# CCM_0020_transmitter.net
KiCad netlist of a schematic drawn in EAGLE
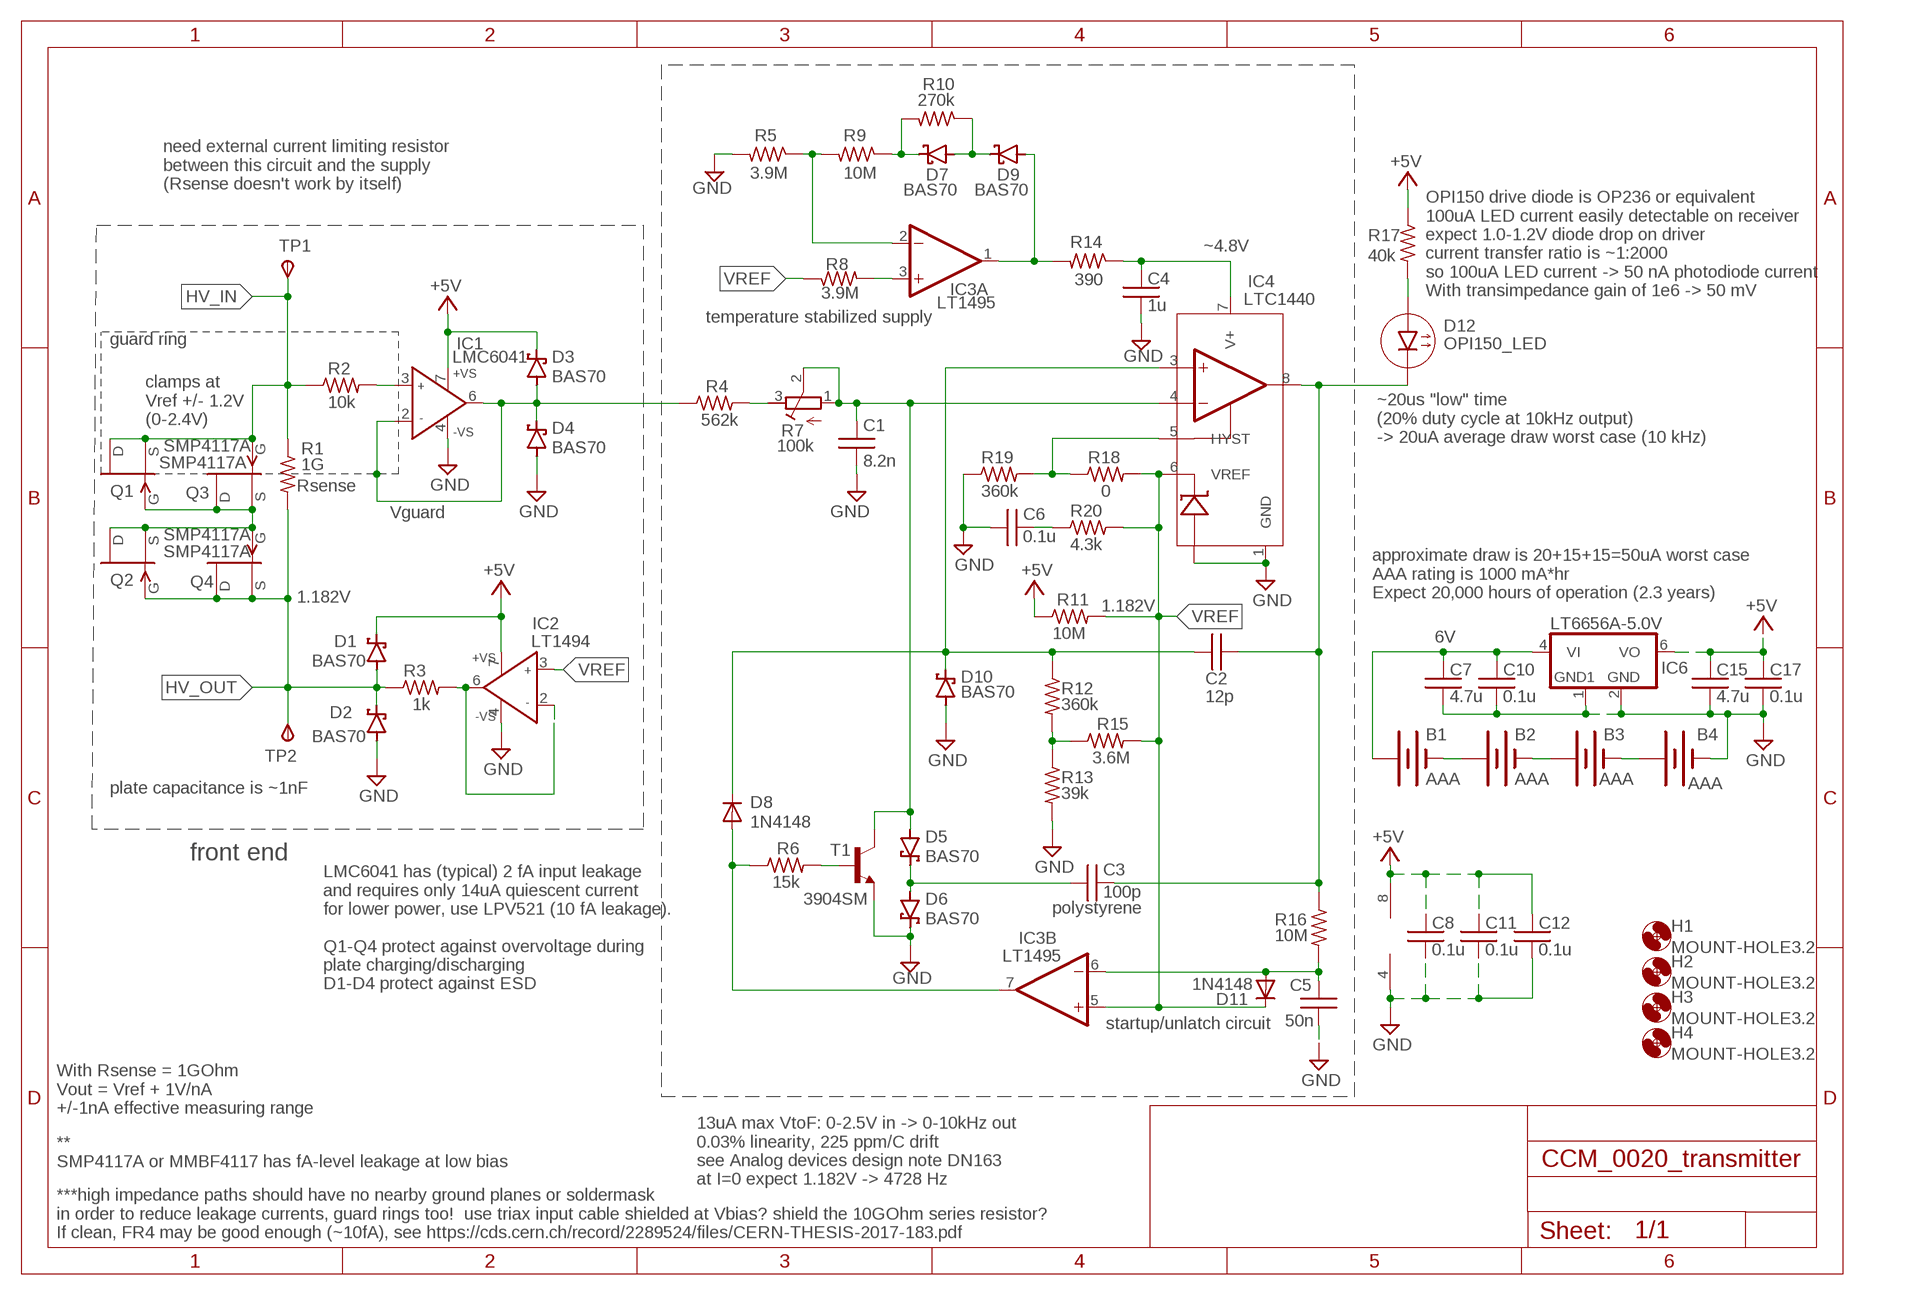
[diagram p0: schematic, sheet 1]

(export (version "E")
  (design (tool "Eeschema 10.0.6"))
  (components
    (comp (ref "B1")
      (value "AAA")
      (footprint "eagle-import:AAA_SM")
      (libsource (lib "eagle-import") (part "AAA"))
    )
    (comp (ref "B2")
      (value "AAA")
      (footprint "eagle-import:AAA_SM")
      (libsource (lib "eagle-import") (part "AAA"))
    )
    (comp (ref "B3")
      (value "AAA")
      (footprint "eagle-import:AAA_SM")
      (libsource (lib "eagle-import") (part "AAA"))
    )
    (comp (ref "B4")
      (value "AAA")
      (footprint "eagle-import:AAA_SM")
      (libsource (lib "eagle-import") (part "AAA"))
    )
    (comp (ref "C1")
      (value "8.2n")
      (footprint "eagle-import:0603")
      (libsource (lib "eagle-import") (part "C0603"))
    )
    (comp (ref "C2")
      (value "12p")
      (footprint "eagle-import:0603")
      (libsource (lib "eagle-import") (part "C0603"))
    )
    (comp (ref "C3")
      (value "100p")
      (footprint "eagle-import:0603")
      (libsource (lib "eagle-import") (part "C0603"))
    )
    (comp (ref "C4")
      (value "1u")
      (footprint "eagle-import:0603")
      (libsource (lib "eagle-import") (part "C0603"))
    )
    (comp (ref "C5")
      (value "50n")
      (footprint "eagle-import:0603")
      (libsource (lib "eagle-import") (part "C0603"))
    )
    (comp (ref "C6")
      (value "0.1u")
      (footprint "eagle-import:0603")
      (libsource (lib "eagle-import") (part "C0603"))
    )
    (comp (ref "C7")
      (value "4.7u")
      (footprint "eagle-import:0603")
      (libsource (lib "eagle-import") (part "C0603"))
    )
    (comp (ref "C8")
      (value "0.1u")
      (footprint "eagle-import:0603")
      (libsource (lib "eagle-import") (part "C0603"))
    )
    (comp (ref "C10")
      (value "0.1u")
      (footprint "eagle-import:0603")
      (libsource (lib "eagle-import") (part "C0603"))
    )
    (comp (ref "C11")
      (value "0.1u")
      (footprint "eagle-import:0603")
      (libsource (lib "eagle-import") (part "C0603"))
    )
    (comp (ref "C12")
      (value "0.1u")
      (footprint "eagle-import:0603")
      (libsource (lib "eagle-import") (part "C0603"))
    )
    (comp (ref "C15")
      (value "4.7u")
      (footprint "eagle-import:0603")
      (libsource (lib "eagle-import") (part "C0603"))
    )
    (comp (ref "C17")
      (value "0.1u")
      (footprint "eagle-import:0603")
      (libsource (lib "eagle-import") (part "C0603"))
    )
    (comp (ref "D1")
      (value "BAS70")
      (footprint "eagle-import:SOT23")
      (libsource (lib "eagle-import") (part "BAS70"))
    )
    (comp (ref "D2")
      (value "BAS70")
      (footprint "eagle-import:SOT23")
      (libsource (lib "eagle-import") (part "BAS70"))
    )
    (comp (ref "D3")
      (value "BAS70")
      (footprint "eagle-import:SOT23")
      (libsource (lib "eagle-import") (part "BAS70"))
    )
    (comp (ref "D4")
      (value "BAS70")
      (footprint "eagle-import:SOT23")
      (libsource (lib "eagle-import") (part "BAS70"))
    )
    (comp (ref "D5")
      (value "BAS70")
      (footprint "eagle-import:SOT23")
      (libsource (lib "eagle-import") (part "BAS70"))
    )
    (comp (ref "D6")
      (value "BAS70")
      (footprint "eagle-import:SOT23")
      (libsource (lib "eagle-import") (part "BAS70"))
    )
    (comp (ref "D7")
      (value "BAS70")
      (footprint "eagle-import:SOT23")
      (libsource (lib "eagle-import") (part "BAS70"))
    )
    (comp (ref "D8")
      (value "1N4148")
      (footprint "eagle-import:SOD323_ST")
      (libsource (lib "eagle-import") (part "1N4148"))
    )
    (comp (ref "D9")
      (value "BAS70")
      (footprint "eagle-import:SOT23")
      (libsource (lib "eagle-import") (part "BAS70"))
    )
    (comp (ref "D10")
      (value "BAS70")
      (footprint "eagle-import:SOT23")
      (libsource (lib "eagle-import") (part "BAS70"))
    )
    (comp (ref "D11")
      (value "1N4148")
      (footprint "eagle-import:SOD323_ST")
      (libsource (lib "eagle-import") (part "1N4148"))
    )
    (comp (ref "D12")
      (value "OPI150_LED")
      (footprint "eagle-import:OPI150_LED")
      (libsource (lib "eagle-import") (part "OPI150_LED"))
    )
    (comp (ref "H1")
      (value "MOUNT-HOLE3.2")
      (footprint "eagle-import:3,2")
      (libsource (lib "eagle-import") (part "MOUNT-HOLE3.2"))
    )
    (comp (ref "H2")
      (value "MOUNT-HOLE3.2")
      (footprint "eagle-import:3,2")
      (libsource (lib "eagle-import") (part "MOUNT-HOLE3.2"))
    )
    (comp (ref "H3")
      (value "MOUNT-HOLE3.2")
      (footprint "eagle-import:3,2")
      (libsource (lib "eagle-import") (part "MOUNT-HOLE3.2"))
    )
    (comp (ref "H4")
      (value "MOUNT-HOLE3.2")
      (footprint "eagle-import:3,2")
      (libsource (lib "eagle-import") (part "MOUNT-HOLE3.2"))
    )
    (comp (ref "IC1")
      (value "LMC6041")
      (footprint "eagle-import:SO08")
      (libsource (lib "eagle-import") (part "AD825_A"))
    )
    (comp (ref "IC2")
      (value "LT1494")
      (footprint "eagle-import:SO08")
      (libsource (lib "eagle-import") (part "AD825_A"))
    )
    (comp (ref "IC3")
      (value "LT1495")
      (footprint "eagle-import:SO08")
      (libsource (lib "eagle-import") (part "LM393D"))
    )
    (comp (ref "IC4")
      (value "LTC1440")
      (footprint "eagle-import:SO8")
      (libsource (lib "eagle-import") (part "LTC1440"))
    )
    (comp (ref "IC6")
      (value "LT6656A-5.0V")
      (footprint "eagle-import:SOT23-6")
      (libsource (lib "eagle-import") (part "LT6656"))
    )
    (comp (ref "Q1")
      (value "SMP4117A")
      (footprint "eagle-import:SOT23")
      (libsource (lib "eagle-import") (part "?548SST4"))
    )
    (comp (ref "Q2")
      (value "SMP4117A")
      (footprint "eagle-import:SOT23")
      (libsource (lib "eagle-import") (part "?548SST4"))
    )
    (comp (ref "Q3")
      (value "SMP4117A")
      (footprint "eagle-import:SOT23")
      (libsource (lib "eagle-import") (part "?548SST4"))
    )
    (comp (ref "Q4")
      (value "SMP4117A")
      (footprint "eagle-import:SOT23")
      (libsource (lib "eagle-import") (part "?548SST4"))
    )
    (comp (ref "R1")
      (value "1G")
      (footprint "eagle-import:2512")
      (libsource (lib "eagle-import") (part "RESISTOR2512"))
    )
    (comp (ref "R2")
      (value "10k")
      (footprint "eagle-import:0603")
      (libsource (lib "eagle-import") (part "R0603"))
    )
    (comp (ref "R3")
      (value "1k")
      (footprint "eagle-import:0603")
      (libsource (lib "eagle-import") (part "R0603"))
    )
    (comp (ref "R4")
      (value "562k")
      (footprint "eagle-import:0603")
      (libsource (lib "eagle-import") (part "R0603"))
    )
    (comp (ref "R5")
      (value "3.9M")
      (footprint "eagle-import:0603")
      (libsource (lib "eagle-import") (part "R0603"))
    )
    (comp (ref "R6")
      (value "15k")
      (footprint "eagle-import:0603")
      (libsource (lib "eagle-import") (part "R0603"))
    )
    (comp (ref "R7")
      (value "100k")
      (footprint "eagle-import:RTRIM64Y")
      (libsource (lib "eagle-import") (part "R-TRIMM64Y"))
    )
    (comp (ref "R8")
      (value "3.9M")
      (footprint "eagle-import:0603")
      (libsource (lib "eagle-import") (part "R0603"))
    )
    (comp (ref "R9")
      (value "10M")
      (footprint "eagle-import:0603")
      (libsource (lib "eagle-import") (part "R0603"))
    )
    (comp (ref "R10")
      (value "270k")
      (footprint "eagle-import:0603")
      (libsource (lib "eagle-import") (part "R0603"))
    )
    (comp (ref "R11")
      (value "10M")
      (footprint "eagle-import:0603")
      (libsource (lib "eagle-import") (part "R0603"))
    )
    (comp (ref "R12")
      (value "360k")
      (footprint "eagle-import:0603")
      (libsource (lib "eagle-import") (part "R0603"))
    )
    (comp (ref "R13")
      (value "39k")
      (footprint "eagle-import:0603")
      (libsource (lib "eagle-import") (part "R0603"))
    )
    (comp (ref "R14")
      (value "390")
      (footprint "eagle-import:0603")
      (libsource (lib "eagle-import") (part "R0603"))
    )
    (comp (ref "R15")
      (value "3.6M")
      (footprint "eagle-import:0603")
      (libsource (lib "eagle-import") (part "R0603"))
    )
    (comp (ref "R16")
      (value "10M")
      (footprint "eagle-import:0603")
      (libsource (lib "eagle-import") (part "R0603"))
    )
    (comp (ref "R17")
      (value "40k")
      (footprint "eagle-import:0603")
      (libsource (lib "eagle-import") (part "R0603"))
    )
    (comp (ref "R18")
      (value "0")
      (footprint "eagle-import:0603")
      (libsource (lib "eagle-import") (part "R0603"))
    )
    (comp (ref "R19")
      (value "360k")
      (footprint "eagle-import:0603")
      (libsource (lib "eagle-import") (part "R0603"))
    )
    (comp (ref "R20")
      (value "4.3k")
      (footprint "eagle-import:0603")
      (libsource (lib "eagle-import") (part "R0603"))
    )
    (comp (ref "T1")
      (value "3904SM")
      (footprint "eagle-import:SOT23")
      (libsource (lib "eagle-import") (part "3904SM"))
    )
    (comp (ref "TP1")
      (value "TPSPAD1-17")
      (footprint "eagle-import:P1-17")
      (libsource (lib "eagle-import") (part "TPSPAD1-17"))
    )
    (comp (ref "TP2")
      (value "TPSPAD1-17")
      (footprint "eagle-import:P1-17")
      (libsource (lib "eagle-import") (part "TPSPAD1-17"))
    )
  )
  (nets
    (net (code "1") (name "+5V") (class "Default")
      (node (ref "C11") (pin "1") (pinfunction "1_1") (pintype "passive"))
      (node (ref "C12") (pin "1") (pinfunction "1_1") (pintype "passive"))
      (node (ref "C15") (pin "1") (pinfunction "1_1") (pintype "passive"))
      (node (ref "C17") (pin "1") (pinfunction "1_1") (pintype "passive"))
      (node (ref "C8") (pin "1") (pinfunction "1_1") (pintype "passive"))
      (node (ref "D1") (pin "3") (pinfunction "C_3") (pintype "passive"))
      (node (ref "D3") (pin "3") (pinfunction "C_3") (pintype "passive"))
      (node (ref "IC1") (pin "7") (pinfunction "+VS_7") (pintype "input"))
      (node (ref "IC2") (pin "7") (pinfunction "+VS_7") (pintype "input"))
      (node (ref "IC3") (pin "8") (pinfunction "V+_8") (pintype "power_in"))
      (node (ref "IC6") (pin "6") (pinfunction "VO_6") (pintype "passive"))
      (node (ref "R11") (pin "1") (pinfunction "1_1") (pintype "passive"))
      (node (ref "R17") (pin "1") (pinfunction "1_1") (pintype "passive"))
    )
    (net (code "2") (name "GND") (class "Default")
      (node (ref "B4") (pin "-") (pinfunction "-_-") (pintype "power_in"))
      (node (ref "C1") (pin "2") (pinfunction "2_2") (pintype "passive"))
      (node (ref "C10") (pin "2") (pinfunction "2_2") (pintype "passive"))
      (node (ref "C11") (pin "2") (pinfunction "2_2") (pintype "passive"))
      (node (ref "C12") (pin "2") (pinfunction "2_2") (pintype "passive"))
      (node (ref "C15") (pin "2") (pinfunction "2_2") (pintype "passive"))
      (node (ref "C17") (pin "2") (pinfunction "2_2") (pintype "passive"))
      (node (ref "C4") (pin "2") (pinfunction "2_2") (pintype "passive"))
      (node (ref "C5") (pin "2") (pinfunction "2_2") (pintype "passive"))
      (node (ref "C6") (pin "1") (pinfunction "1_1") (pintype "passive"))
      (node (ref "C7") (pin "2") (pinfunction "2_2") (pintype "passive"))
      (node (ref "C8") (pin "2") (pinfunction "2_2") (pintype "passive"))
      (node (ref "D10") (pin "1") (pinfunction "A_1") (pintype "passive"))
      (node (ref "D2") (pin "1") (pinfunction "A_1") (pintype "passive"))
      (node (ref "D4") (pin "1") (pinfunction "A_1") (pintype "passive"))
      (node (ref "D6") (pin "3") (pinfunction "C_3") (pintype "passive"))
      (node (ref "IC1") (pin "4") (pinfunction "-VS_4") (pintype "input"))
      (node (ref "IC2") (pin "4") (pinfunction "-VS_4") (pintype "input"))
      (node (ref "IC3") (pin "4") (pinfunction "V-_4") (pintype "power_in"))
      (node (ref "IC4") (pin "1") (pinfunction "GND_1") (pintype "power_in"))
      (node (ref "IC4") (pin "2") (pinfunction "V-_2") (pintype "passive"))
      (node (ref "IC6") (pin "1") (pinfunction "GND1_1") (pintype "passive"))
      (node (ref "IC6") (pin "2") (pinfunction "GND_2") (pintype "passive"))
      (node (ref "R13") (pin "2") (pinfunction "2_2") (pintype "passive"))
      (node (ref "R19") (pin "1") (pinfunction "1_1") (pintype "passive"))
      (node (ref "R5") (pin "2") (pinfunction "2_2") (pintype "passive"))
      (node (ref "T1") (pin "2") (pinfunction "E_2") (pintype "passive"))
    )
    (net (code "3") (name "HV_IN") (class "Default")
      (node (ref "Q1") (pin "1") (pinfunction "D_1") (pintype "passive"))
      (node (ref "Q1") (pin "2") (pinfunction "S_2") (pintype "passive"))
      (node (ref "Q3") (pin "3") (pinfunction "G_3") (pintype "passive"))
      (node (ref "R1") (pin "1") (pinfunction "1_1") (pintype "passive"))
      (node (ref "R2") (pin "1") (pinfunction "1_1") (pintype "passive"))
      (node (ref "TP1") (pin "TP") (pinfunction "PP_TP") (pintype "input"))
    )
    (net (code "4") (name "HV_OUT") (class "Default")
      (node (ref "D1") (pin "1") (pinfunction "A_1") (pintype "passive"))
      (node (ref "D2") (pin "3") (pinfunction "C_3") (pintype "passive"))
      (node (ref "Q2") (pin "3") (pinfunction "G_3") (pintype "passive"))
      (node (ref "Q4") (pin "1") (pinfunction "D_1") (pintype "passive"))
      (node (ref "Q4") (pin "2") (pinfunction "S_2") (pintype "passive"))
      (node (ref "R1") (pin "2") (pinfunction "2_2") (pintype "passive"))
      (node (ref "R3") (pin "1") (pinfunction "1_1") (pintype "passive"))
      (node (ref "TP2") (pin "TP") (pinfunction "PP_TP") (pintype "input"))
    )
    (net (code "5") (name "Net-(B1-Pad-)") (class "Default")
      (node (ref "B1") (pin "-") (pinfunction "-_-") (pintype "power_in"))
      (node (ref "B2") (pin "+") (pinfunction "+_+") (pintype "power_in"))
    )
    (net (code "6") (name "Net-(B2-Pad-)") (class "Default")
      (node (ref "B2") (pin "-") (pinfunction "-_-") (pintype "power_in"))
      (node (ref "B3") (pin "+") (pinfunction "+_+") (pintype "power_in"))
    )
    (net (code "7") (name "Net-(B3-Pad-)") (class "Default")
      (node (ref "B3") (pin "-") (pinfunction "-_-") (pintype "power_in"))
      (node (ref "B4") (pin "+") (pinfunction "+_+") (pintype "power_in"))
    )
    (net (code "8") (name "Net-(C6-Pad2)") (class "Default")
      (node (ref "C6") (pin "2") (pinfunction "2_2") (pintype "passive"))
      (node (ref "R20") (pin "1") (pinfunction "1_1") (pintype "passive"))
    )
    (net (code "9") (name "Net-(D3-A)") (class "Default")
      (node (ref "D3") (pin "1") (pinfunction "A_1") (pintype "passive"))
      (node (ref "D4") (pin "3") (pinfunction "C_3") (pintype "passive"))
      (node (ref "IC1") (pin "2") (pinfunction "IN-_2") (pintype "input"))
      (node (ref "IC1") (pin "6") (pinfunction "OUT_6") (pintype "output"))
      (node (ref "R4") (pin "1") (pinfunction "1_1") (pintype "passive"))
    )
    (net (code "10") (name "Net-(D5-A)") (class "Default")
      (node (ref "C1") (pin "1") (pinfunction "1_1") (pintype "passive"))
      (node (ref "D5") (pin "1") (pinfunction "A_1") (pintype "passive"))
      (node (ref "IC4") (pin "4") (pinfunction "-IN_4") (pintype "input"))
      (node (ref "R7") (pin "1") (pinfunction "A_1") (pintype "passive"))
      (node (ref "R7") (pin "2") (pinfunction "S_2") (pintype "passive"))
      (node (ref "T1") (pin "3") (pinfunction "C_3") (pintype "passive"))
    )
    (net (code "11") (name "Net-(D5-C)") (class "Default")
      (node (ref "C3") (pin "1") (pinfunction "1_1") (pintype "passive"))
      (node (ref "D5") (pin "3") (pinfunction "C_3") (pintype "passive"))
      (node (ref "D6") (pin "1") (pinfunction "A_1") (pintype "passive"))
    )
    (net (code "12") (name "Net-(D7-A)") (class "Default")
      (node (ref "D7") (pin "1") (pinfunction "A_1") (pintype "passive"))
      (node (ref "D9") (pin "3") (pinfunction "C_3") (pintype "passive"))
      (node (ref "R10") (pin "1") (pinfunction "1_1") (pintype "passive"))
    )
    (net (code "13") (name "Net-(D7-C)") (class "Default")
      (node (ref "D7") (pin "3") (pinfunction "C_3") (pintype "passive"))
      (node (ref "R10") (pin "2") (pinfunction "2_2") (pintype "passive"))
      (node (ref "R9") (pin "1") (pinfunction "1_1") (pintype "passive"))
    )
    (net (code "14") (name "Net-(D9-A)") (class "Default")
      (node (ref "D9") (pin "1") (pinfunction "A_1") (pintype "passive"))
      (node (ref "IC3") (pin "1") (pinfunction "OUT_1") (pintype "output"))
      (node (ref "R14") (pin "2") (pinfunction "2_2") (pintype "passive"))
    )
    (net (code "15") (name "Net-(D10-C)") (class "Default")
      (node (ref "C2") (pin "1") (pinfunction "1_1") (pintype "passive"))
      (node (ref "D10") (pin "3") (pinfunction "C_3") (pintype "passive"))
      (node (ref "D8") (pin "C") (pinfunction "C_C") (pintype "passive"))
      (node (ref "IC4") (pin "3") (pinfunction "+IN_3") (pintype "input"))
      (node (ref "R12") (pin "1") (pinfunction "1_1") (pintype "passive"))
    )
    (net (code "16") (name "Net-(D12-1(A))") (class "Default")
      (node (ref "D12") (pin "P$1") (pinfunction "1(A)_P$1") (pintype "passive"))
      (node (ref "R17") (pin "2") (pinfunction "2_2") (pintype "passive"))
    )
    (net (code "17") (name "Net-(D12-2(C))") (class "Default")
      (node (ref "C2") (pin "2") (pinfunction "2_2") (pintype "passive"))
      (node (ref "C3") (pin "2") (pinfunction "2_2") (pintype "passive"))
      (node (ref "D12") (pin "P$2") (pinfunction "2(C)_P$2") (pintype "passive"))
      (node (ref "IC4") (pin "8") (pinfunction "OUT_8") (pintype "output"))
      (node (ref "R16") (pin "1") (pinfunction "1_1") (pintype "passive"))
    )
    (net (code "18") (name "Net-(IC1-IN+)") (class "Default")
      (node (ref "IC1") (pin "3") (pinfunction "IN+_3") (pintype "input"))
      (node (ref "R2") (pin "2") (pinfunction "2_2") (pintype "passive"))
    )
    (net (code "19") (name "Net-(IC2-IN-)") (class "Default")
      (node (ref "IC2") (pin "2") (pinfunction "IN-_2") (pintype "input"))
      (node (ref "IC2") (pin "6") (pinfunction "OUT_6") (pintype "output"))
      (node (ref "R3") (pin "2") (pinfunction "2_2") (pintype "passive"))
    )
    (net (code "20") (name "Net-(IC3A-+IN)") (class "Default")
      (node (ref "IC3") (pin "3") (pinfunction "+IN_3") (pintype "input"))
      (node (ref "R8") (pin "2") (pinfunction "2_2") (pintype "passive"))
    )
    (net (code "21") (name "Net-(IC3A--IN)") (class "Default")
      (node (ref "IC3") (pin "2") (pinfunction "-IN_2") (pintype "input"))
      (node (ref "R5") (pin "1") (pinfunction "1_1") (pintype "passive"))
      (node (ref "R9") (pin "2") (pinfunction "2_2") (pintype "passive"))
    )
    (net (code "22") (name "Net-(IC3B--IN)") (class "Default")
      (node (ref "C5") (pin "1") (pinfunction "1_1") (pintype "passive"))
      (node (ref "D11") (pin "A") (pinfunction "A_A") (pintype "passive"))
      (node (ref "IC3") (pin "6") (pinfunction "-IN_6") (pintype "input"))
      (node (ref "R16") (pin "2") (pinfunction "2_2") (pintype "passive"))
    )
    (net (code "23") (name "Net-(IC3B-OUT)") (class "Default")
      (node (ref "D8") (pin "A") (pinfunction "A_A") (pintype "passive"))
      (node (ref "IC3") (pin "7") (pinfunction "OUT_7") (pintype "output"))
      (node (ref "R6") (pin "1") (pinfunction "1_1") (pintype "passive"))
    )
    (net (code "24") (name "Net-(IC4-HYST)") (class "Default")
      (node (ref "IC4") (pin "5") (pinfunction "HYST_5") (pintype "input"))
      (node (ref "R18") (pin "1") (pinfunction "1_1") (pintype "passive"))
      (node (ref "R19") (pin "2") (pinfunction "2_2") (pintype "passive"))
    )
    (net (code "25") (name "Net-(IC4-V+)") (class "Default")
      (node (ref "C4") (pin "1") (pinfunction "1_1") (pintype "passive"))
      (node (ref "IC4") (pin "7") (pinfunction "V+_7") (pintype "power_in"))
      (node (ref "R14") (pin "1") (pinfunction "1_1") (pintype "passive"))
    )
    (net (code "26") (name "Net-(IC6-VI)") (class "Default")
      (node (ref "B1") (pin "+") (pinfunction "+_+") (pintype "power_in"))
      (node (ref "C10") (pin "1") (pinfunction "1_1") (pintype "passive"))
      (node (ref "C7") (pin "1") (pinfunction "1_1") (pintype "passive"))
      (node (ref "IC6") (pin "4") (pinfunction "VI_4") (pintype "input"))
    )
    (net (code "27") (name "Net-(Q1-G)") (class "Default")
      (node (ref "Q1") (pin "3") (pinfunction "G_3") (pintype "passive"))
      (node (ref "Q2") (pin "1") (pinfunction "D_1") (pintype "passive"))
      (node (ref "Q2") (pin "2") (pinfunction "S_2") (pintype "passive"))
      (node (ref "Q3") (pin "1") (pinfunction "D_1") (pintype "passive"))
      (node (ref "Q3") (pin "2") (pinfunction "S_2") (pintype "passive"))
      (node (ref "Q4") (pin "3") (pinfunction "G_3") (pintype "passive"))
    )
    (net (code "28") (name "Net-(R7-E)") (class "Default")
      (node (ref "R4") (pin "2") (pinfunction "2_2") (pintype "passive"))
      (node (ref "R7") (pin "3") (pinfunction "E_3") (pintype "passive"))
    )
    (net (code "29") (name "Net-(R12-Pad2)") (class "Default")
      (node (ref "R12") (pin "2") (pinfunction "2_2") (pintype "passive"))
      (node (ref "R13") (pin "1") (pinfunction "1_1") (pintype "passive"))
      (node (ref "R15") (pin "1") (pinfunction "1_1") (pintype "passive"))
    )
    (net (code "30") (name "Net-(T1-B)") (class "Default")
      (node (ref "R6") (pin "2") (pinfunction "2_2") (pintype "passive"))
      (node (ref "T1") (pin "1") (pinfunction "B_1") (pintype "passive"))
    )
    (net (code "31") (name "VREF") (class "Default")
      (node (ref "D11") (pin "C") (pinfunction "C_C") (pintype "passive"))
      (node (ref "IC2") (pin "3") (pinfunction "IN+_3") (pintype "input"))
      (node (ref "IC3") (pin "5") (pinfunction "+IN_5") (pintype "input"))
      (node (ref "IC4") (pin "6") (pinfunction "VREF_6") (pintype "passive"))
      (node (ref "R11") (pin "2") (pinfunction "2_2") (pintype "passive"))
      (node (ref "R15") (pin "2") (pinfunction "2_2") (pintype "passive"))
      (node (ref "R18") (pin "2") (pinfunction "2_2") (pintype "passive"))
      (node (ref "R20") (pin "2") (pinfunction "2_2") (pintype "passive"))
      (node (ref "R8") (pin "1") (pinfunction "1_1") (pintype "passive"))
    )
  )
)
